# remote_pwr.net
KiCad netlist of a schematic drawn in EAGLE
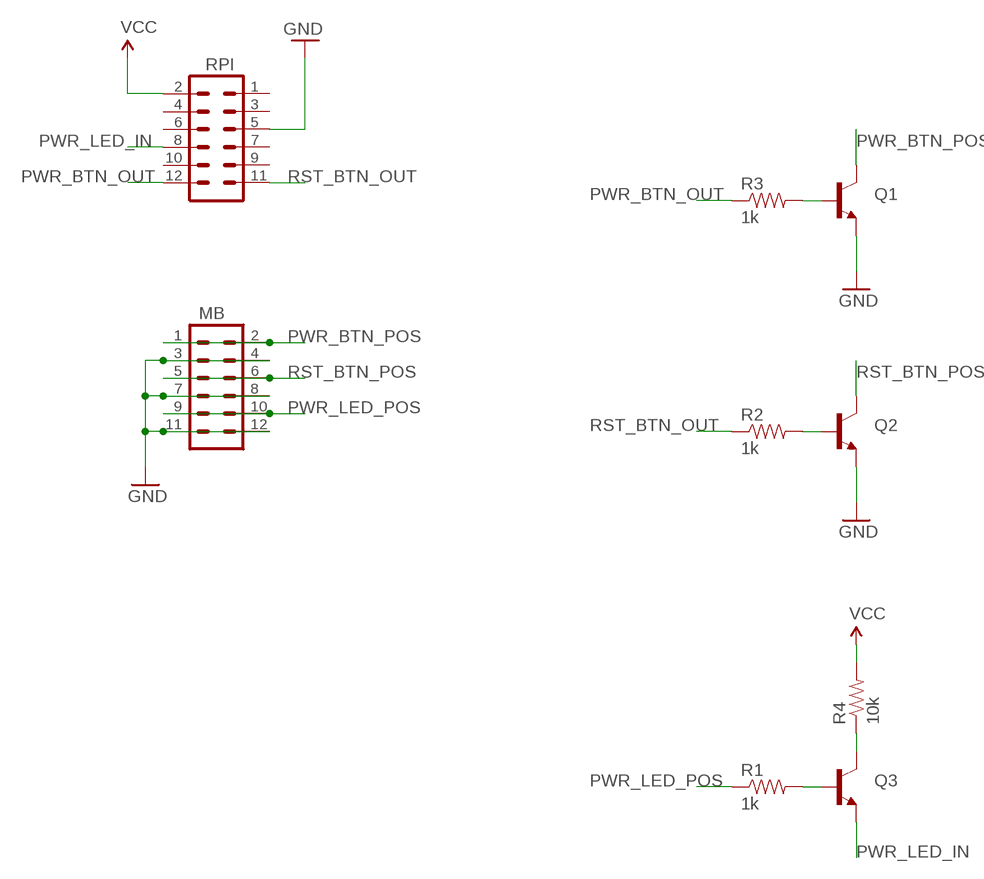
[diagram p0: schematic, sheet 1]

(export (version "E")
  (design (tool "Eeschema 10.0.6"))
  (components
    (comp (ref "MB")
      (value "M06X2PTH_FEMALE")
      (footprint "eagle-import:2X6")
      (libsource (lib "eagle-import") (part "M06X2PTH_FEMALE"))
    )
    (comp (ref "Q1")
      (value "TRANSISTOR_NPNTO-92-AMMO")
      (footprint "eagle-import:TO-92-AMMO")
      (libsource (lib "eagle-import") (part "TRANSISTOR_NPNTO-92-AMMO"))
    )
    (comp (ref "Q2")
      (value "TRANSISTOR_NPNTO-92-AMMO")
      (footprint "eagle-import:TO-92-AMMO")
      (libsource (lib "eagle-import") (part "TRANSISTOR_NPNTO-92-AMMO"))
    )
    (comp (ref "Q3")
      (value "TRANSISTOR_NPNTO-92-AMMO")
      (footprint "eagle-import:TO-92-AMMO")
      (libsource (lib "eagle-import") (part "TRANSISTOR_NPNTO-92-AMMO"))
    )
    (comp (ref "R1")
      (value "1k")
      (footprint "eagle-import:AXIAL-0.3")
      (libsource (lib "eagle-import") (part "RESISTORAXIAL-0.3"))
    )
    (comp (ref "R2")
      (value "1k")
      (footprint "eagle-import:AXIAL-0.3")
      (libsource (lib "eagle-import") (part "RESISTORAXIAL-0.3"))
    )
    (comp (ref "R3")
      (value "1k")
      (footprint "eagle-import:AXIAL-0.3")
      (libsource (lib "eagle-import") (part "RESISTORAXIAL-0.3"))
    )
    (comp (ref "R4")
      (value "10k")
      (footprint "eagle-import:AXIAL-0.3")
      (libsource (lib "eagle-import") (part "RESISTORAXIAL-0.3"))
    )
    (comp (ref "RPI")
      (value "M06X2PTH_FEMALE")
      (footprint "eagle-import:2X6")
      (libsource (lib "eagle-import") (part "M06X2PTH_FEMALE"))
    )
  )
  (nets
    (net (code "1") (name "/PWR_BTN_OUT") (class "Default")
      (node (ref "R3") (pin "P$1") (pinfunction "1_P$1") (pintype "passive"))
      (node (ref "RPI") (pin "12") (pinfunction "12_12") (pintype "passive"))
    )
    (net (code "2") (name "/PWR_BTN_POS") (class "Default")
      (node (ref "MB") (pin "1") (pinfunction "1_1") (pintype "passive"))
      (node (ref "MB") (pin "2") (pinfunction "2_2") (pintype "passive"))
      (node (ref "Q1") (pin "3") (pinfunction "C_3") (pintype "passive"))
    )
    (net (code "3") (name "/PWR_LED_IN") (class "Default")
      (node (ref "Q3") (pin "1") (pinfunction "E_1") (pintype "passive"))
      (node (ref "RPI") (pin "8") (pinfunction "8_8") (pintype "passive"))
    )
    (net (code "4") (name "/PWR_LED_POS") (class "Default")
      (node (ref "MB") (pin "10") (pinfunction "10_10") (pintype "passive"))
      (node (ref "MB") (pin "9") (pinfunction "9_9") (pintype "passive"))
      (node (ref "R1") (pin "P$1") (pinfunction "1_P$1") (pintype "passive"))
    )
    (net (code "5") (name "/RST_BTN_OUT") (class "Default")
      (node (ref "R2") (pin "P$1") (pinfunction "1_P$1") (pintype "passive"))
      (node (ref "RPI") (pin "11") (pinfunction "11_11") (pintype "passive"))
    )
    (net (code "6") (name "/RST_BTN_POS") (class "Default")
      (node (ref "MB") (pin "5") (pinfunction "5_5") (pintype "passive"))
      (node (ref "MB") (pin "6") (pinfunction "6_6") (pintype "passive"))
      (node (ref "Q2") (pin "3") (pinfunction "C_3") (pintype "passive"))
    )
    (net (code "7") (name "GND") (class "Default")
      (node (ref "MB") (pin "11") (pinfunction "11_11") (pintype "passive"))
      (node (ref "MB") (pin "12") (pinfunction "12_12") (pintype "passive"))
      (node (ref "MB") (pin "3") (pinfunction "3_3") (pintype "passive"))
      (node (ref "MB") (pin "4") (pinfunction "4_4") (pintype "passive"))
      (node (ref "MB") (pin "7") (pinfunction "7_7") (pintype "passive"))
      (node (ref "MB") (pin "8") (pinfunction "8_8") (pintype "passive"))
      (node (ref "Q1") (pin "1") (pinfunction "E_1") (pintype "passive"))
      (node (ref "Q2") (pin "1") (pinfunction "E_1") (pintype "passive"))
      (node (ref "RPI") (pin "5") (pinfunction "5_5") (pintype "passive"))
    )
    (net (code "8") (name "Net-(Q1-B)") (class "Default")
      (node (ref "Q1") (pin "2") (pinfunction "B_2") (pintype "passive"))
      (node (ref "R3") (pin "P$2") (pinfunction "2_P$2") (pintype "passive"))
    )
    (net (code "9") (name "Net-(Q2-B)") (class "Default")
      (node (ref "Q2") (pin "2") (pinfunction "B_2") (pintype "passive"))
      (node (ref "R2") (pin "P$2") (pinfunction "2_P$2") (pintype "passive"))
    )
    (net (code "10") (name "Net-(Q3-B)") (class "Default")
      (node (ref "Q3") (pin "2") (pinfunction "B_2") (pintype "passive"))
      (node (ref "R1") (pin "P$2") (pinfunction "2_P$2") (pintype "passive"))
    )
    (net (code "11") (name "Net-(Q3-C)") (class "Default")
      (node (ref "Q3") (pin "3") (pinfunction "C_3") (pintype "passive"))
      (node (ref "R4") (pin "P$1") (pinfunction "1_P$1") (pintype "passive"))
    )
    (net (code "12") (name "VCC") (class "Default")
      (node (ref "R4") (pin "P$2") (pinfunction "2_P$2") (pintype "passive"))
      (node (ref "RPI") (pin "2") (pinfunction "2_2") (pintype "passive"))
    )
    (net (code "13") (name "unconnected-(RPI-Pad1)") (class "Default")
      (node (ref "RPI") (pin "1") (pinfunction "1_1") (pintype "passive"))
    )
    (net (code "14") (name "unconnected-(RPI-Pad3)") (class "Default")
      (node (ref "RPI") (pin "3") (pinfunction "3_3") (pintype "passive"))
    )
    (net (code "15") (name "unconnected-(RPI-Pad4)") (class "Default")
      (node (ref "RPI") (pin "4") (pinfunction "4_4") (pintype "passive"))
    )
    (net (code "16") (name "unconnected-(RPI-Pad6)") (class "Default")
      (node (ref "RPI") (pin "6") (pinfunction "6_6") (pintype "passive"))
    )
    (net (code "17") (name "unconnected-(RPI-Pad7)") (class "Default")
      (node (ref "RPI") (pin "7") (pinfunction "7_7") (pintype "passive"))
    )
    (net (code "18") (name "unconnected-(RPI-Pad9)") (class "Default")
      (node (ref "RPI") (pin "9") (pinfunction "9_9") (pintype "passive"))
    )
    (net (code "19") (name "unconnected-(RPI-Pad10)") (class "Default")
      (node (ref "RPI") (pin "10") (pinfunction "10_10") (pintype "passive"))
    )
  )
)
